# new_JTAG_to_HDMI.net
KiCad netlist of a schematic drawn in Altium Designer
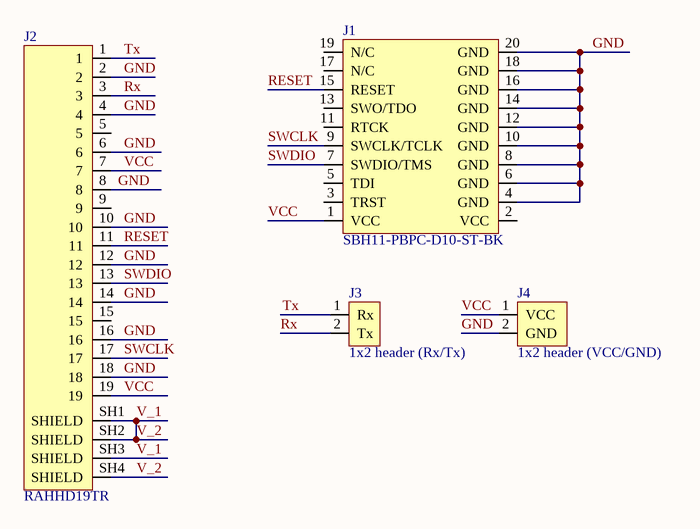
[diagram p0: new_JTAG_to_HDMI.SchDoc]

(export (version "E")
  (design (tool "Eeschema 10.0.6"))
  (components
    (comp (ref "J1")
      (value "SBH11-PBPC-D10-ST-BK")
      (footprint "SBH11-PBPC-D10-ST-BK")
      (description "Conn Shrouded Header (4 Sides) HDR 20 POS 2.54mm Solder ST Top Entry Thru-Hole")
      (fields (field (name "MANUFACTURER") "Sullins"))
      (libsource (lib "JTAG_to_HDMI") (part "SBH11-PBPC-D10-ST-BK"))
    )
    (comp (ref "J2")
      (value "RAHHD19TR")
      (footprint "SWITCHCRAFT_RAHHD19TR")
      (description "HDMI HDMI 2.0 Receptacle Connector 19 Position Surface Mount, Right Angle; Through Hole")
      (fields (field (name "MF") "Switchcraft Inc."))
      (libsource (lib "JTAG_to_HDMI") (part "RAHHD19TR"))
    )
    (comp (ref "J3")
      (value "1x2 header (Rx/Tx)")
      (footprint "DS1021-1*2SF1-1")
      (fields
        (field (name "MANUFACTURER") "Ningbo Connfly Electric")
        (field (name "MANUFACTURER PART NUMBER") "DS1021-1*2SF1-1")
      )
      (libsource (lib "JTAG_to_HDMI") (part "DS1021-1*2SF1-1_1"))
    )
    (comp (ref "J4")
      (value "1x2 header (VCC/GND)")
      (footprint "DS1021-1*2SF1-1")
      (fields
        (field (name "MANUFACTURER") "Ningbo Connfly Electric")
        (field (name "MANUFACTURER PART NUMBER") "DS1021-1*2SF1-1")
      )
      (libsource (lib "JTAG_to_HDMI") (part "DS1021-1*2SF1-1"))
    )
  )
  (nets
    (net (code "1") (name "/GND") (class "Default")
      (node (ref "J1") (pin "10") (pinfunction "GND_10") (pintype "passive"))
      (node (ref "J1") (pin "12") (pinfunction "GND_12") (pintype "passive"))
      (node (ref "J1") (pin "14") (pinfunction "GND_14") (pintype "passive"))
      (node (ref "J1") (pin "16") (pinfunction "GND_16") (pintype "passive"))
      (node (ref "J1") (pin "18") (pinfunction "GND_18") (pintype "passive"))
      (node (ref "J1") (pin "20") (pinfunction "GND_20") (pintype "passive"))
      (node (ref "J1") (pin "4") (pinfunction "GND_4") (pintype "passive"))
      (node (ref "J1") (pin "6") (pinfunction "GND_6") (pintype "passive"))
      (node (ref "J1") (pin "8") (pinfunction "GND_8") (pintype "passive"))
      (node (ref "J2") (pin "10") (pinfunction "10_10") (pintype "passive"))
      (node (ref "J2") (pin "12") (pinfunction "12_12") (pintype "passive"))
      (node (ref "J2") (pin "14") (pinfunction "14_14") (pintype "passive"))
      (node (ref "J2") (pin "16") (pinfunction "16_16") (pintype "passive"))
      (node (ref "J2") (pin "18") (pinfunction "18_18") (pintype "passive"))
      (node (ref "J2") (pin "2") (pinfunction "2_2") (pintype "passive"))
      (node (ref "J2") (pin "4") (pinfunction "4_4") (pintype "passive"))
      (node (ref "J2") (pin "6") (pinfunction "6_6") (pintype "passive"))
      (node (ref "J2") (pin "8") (pinfunction "8_8") (pintype "passive"))
      (node (ref "J4") (pin "2") (pinfunction "GND_2") (pintype "passive"))
    )
    (net (code "2") (name "/RESET") (class "Default")
      (node (ref "J1") (pin "15") (pinfunction "RESET_15") (pintype "passive"))
      (node (ref "J2") (pin "11") (pinfunction "11_11") (pintype "passive"))
    )
    (net (code "3") (name "/Rx") (class "Default")
      (node (ref "J2") (pin "3") (pinfunction "3_3") (pintype "passive"))
      (node (ref "J3") (pin "2") (pinfunction "Tx_2") (pintype "passive"))
    )
    (net (code "4") (name "/SWCLK") (class "Default")
      (node (ref "J1") (pin "9") (pinfunction "SWCLK/TCLK_9") (pintype "passive"))
      (node (ref "J2") (pin "17") (pinfunction "17_17") (pintype "passive"))
    )
    (net (code "5") (name "/SWDIO") (class "Default")
      (node (ref "J1") (pin "7") (pinfunction "SWDIO/TMS_7") (pintype "passive"))
      (node (ref "J2") (pin "13") (pinfunction "13_13") (pintype "passive"))
    )
    (net (code "6") (name "/Tx") (class "Default")
      (node (ref "J2") (pin "1") (pinfunction "1_1") (pintype "passive"))
      (node (ref "J3") (pin "1") (pinfunction "Rx_1") (pintype "passive"))
    )
    (net (code "7") (name "/VCC") (class "Default")
      (node (ref "J1") (pin "1") (pinfunction "VCC_1") (pintype "passive"))
      (node (ref "J2") (pin "19") (pinfunction "19_19") (pintype "passive"))
      (node (ref "J2") (pin "7") (pinfunction "7_7") (pintype "passive"))
      (node (ref "J4") (pin "1") (pinfunction "VCC_1") (pintype "passive"))
    )
    (net (code "8") (name "/V_1") (class "Default")
      (node (ref "J2") (pin "SH1") (pinfunction "SHIELD_SH1") (pintype "passive"))
      (node (ref "J2") (pin "SH2") (pinfunction "SHIELD_SH2") (pintype "passive"))
      (node (ref "J2") (pin "SH3") (pinfunction "SHIELD_SH3") (pintype "passive"))
      (node (ref "J2") (pin "SH4") (pinfunction "SHIELD_SH4") (pintype "passive"))
    )
    (net (code "9") (name "unconnected-(J1-N{slash}C-Pad17)") (class "Default")
      (node (ref "J1") (pin "17") (pinfunction "N/C_17") (pintype "passive"))
    )
    (net (code "10") (name "unconnected-(J1-N{slash}C-Pad19)") (class "Default")
      (node (ref "J1") (pin "19") (pinfunction "N/C_19") (pintype "passive"))
    )
    (net (code "11") (name "unconnected-(J1-RTCK-Pad11)") (class "Default")
      (node (ref "J1") (pin "11") (pinfunction "RTCK_11") (pintype "passive"))
    )
    (net (code "12") (name "unconnected-(J1-SWO{slash}TDO-Pad13)") (class "Default")
      (node (ref "J1") (pin "13") (pinfunction "SWO/TDO_13") (pintype "passive"))
    )
    (net (code "13") (name "unconnected-(J1-TDI-Pad5)") (class "Default")
      (node (ref "J1") (pin "5") (pinfunction "TDI_5") (pintype "passive"))
    )
    (net (code "14") (name "unconnected-(J1-TRST-Pad3)") (class "Default")
      (node (ref "J1") (pin "3") (pinfunction "TRST_3") (pintype "passive"))
    )
    (net (code "15") (name "unconnected-(J1-VCC-Pad2)") (class "Default")
      (node (ref "J1") (pin "2") (pinfunction "VCC_2") (pintype "passive"))
    )
    (net (code "16") (name "unconnected-(J2-Pad5)") (class "Default")
      (node (ref "J2") (pin "5") (pinfunction "5_5") (pintype "passive"))
    )
    (net (code "17") (name "unconnected-(J2-Pad9)") (class "Default")
      (node (ref "J2") (pin "9") (pinfunction "9_9") (pintype "passive"))
    )
    (net (code "18") (name "unconnected-(J2-Pad15)") (class "Default")
      (node (ref "J2") (pin "15") (pinfunction "15_15") (pintype "passive"))
    )
  )
)
